# Powerbank_schematic.net
KiCad netlist of a schematic drawn in Altium Designer
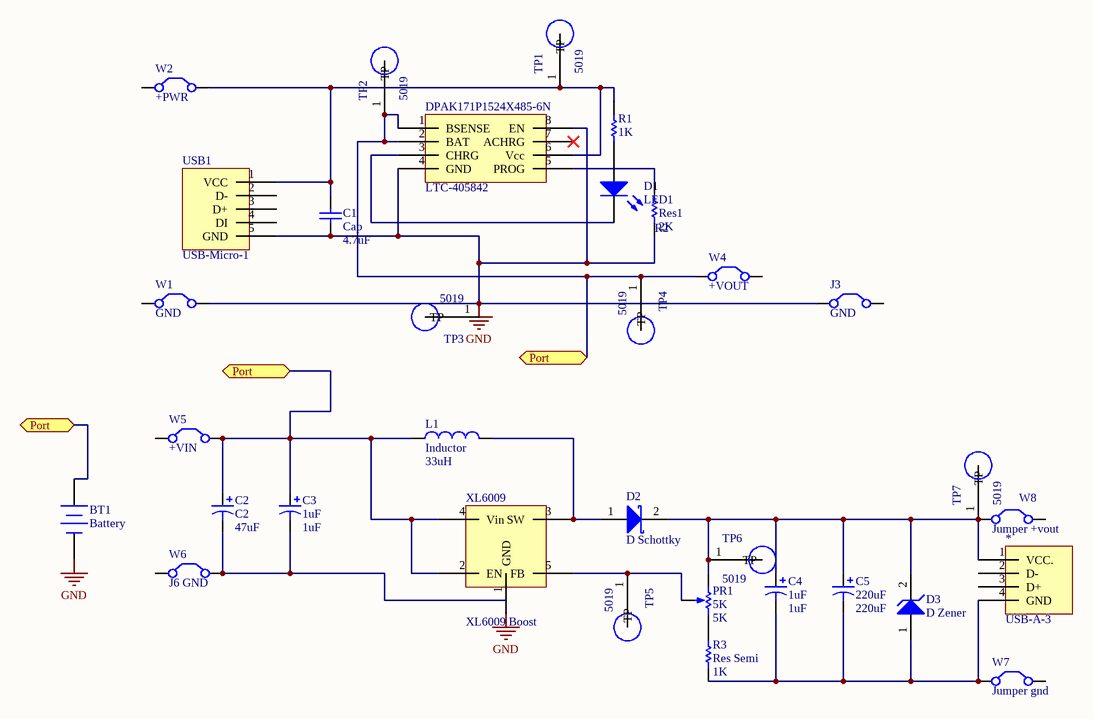
[diagram p0: Powerbank_schematic.SchDoc]

(export (version "E")
  (design (tool "Eeschema 10.0.6"))
  (components
    (comp (ref "*") (value "USB-A-3") (footprint "USB3") (libsource (lib "PCB_Project") (part "USB-A-3")))
    (comp (ref "BT1")
      (value "Battery")
      (footprint "BAT-2")
      (description "Multicell Battery")
      (fields (field (name "PUBLISHER") "Altium Limited"))
      (libsource (lib "Miscellaneous Devices") (part "Battery"))
    )
    (comp (ref "C1")
      (value "Cap")
      (footprint "RAD-0.3")
      (description "Capacitor")
      (fields (field (name "ALTIUM_VALUE") "4.7uF") (field (name "PUBLISHER") "Altium Limited"))
      (libsource (lib "Miscellaneous Devices") (part "Cap"))
    )
    (comp (ref "C2")
      (value "C2")
      (footprint "C0805")
      (description "Polarized Capacitor (Surface Mount)")
      (fields (field (name "ALTIUM_VALUE") "47uF") (field (name "PUBLISHER") "Altium Limited"))
      (libsource (lib "Miscellaneous Devices") (part "Cap Pol3"))
    )
    (comp (ref "C3")
      (value "1uF")
      (footprint "C0805")
      (description "Polarized Capacitor (Surface Mount)")
      (fields (field (name "ALTIUM_VALUE") "1uF") (field (name "PUBLISHER") "Altium Limited"))
      (libsource (lib "Miscellaneous Devices") (part "Cap Pol3"))
    )
    (comp (ref "C4")
      (value "1uF")
      (footprint "C0805")
      (description "Polarized Capacitor (Surface Mount)")
      (fields (field (name "ALTIUM_VALUE") "1uF") (field (name "PUBLISHER") "Altium Limited"))
      (libsource (lib "Miscellaneous Devices") (part "Cap Pol3"))
    )
    (comp (ref "C5")
      (value "220uF")
      (footprint "C0805")
      (description "Polarized Capacitor (Surface Mount)")
      (fields (field (name "ALTIUM_VALUE") "220uF") (field (name "PUBLISHER") "Altium Limited"))
      (libsource (lib "Miscellaneous Devices") (part "Cap Pol3"))
    )
    (comp (ref "D1")
      (value "LED1")
      (footprint "LED-1")
      (description "Typical RED GaAs LED")
      (fields (field (name "PUBLISHER") "Altium Limited"))
      (libsource (lib "Miscellaneous Devices") (part "LED1"))
    )
    (comp (ref "D2")
      (value "D Schottky")
      (footprint "SMB")
      (description "Schottky Diode")
      (fields (field (name "PUBLISHER") "Altium Limited"))
      (libsource (lib "Miscellaneous Devices") (part "D Schottky"))
    )
    (comp (ref "D3")
      (value "D Zener")
      (footprint "DIODE-0.7")
      (description "Zener Diode")
      (fields (field (name "PUBLISHER") "Altium Limited"))
      (libsource (lib "Miscellaneous Devices") (part "D Zener"))
    )
    (comp (ref "DPAK171P1524X485-6N")
      (value "LTC-405842")
      (footprint "DFN-8_DD")
      (libsource (lib "PCB_Project") (part "LTC-405842"))
    )
    (comp (ref "J3")
      (value "GND")
      (footprint "RAD-0.2")
      (description "Jumper Wire")
      (fields (field (name "PUBLISHER") "Altium Limited"))
      (libsource (lib "Miscellaneous Devices") (part "Jumper"))
    )
    (comp (ref "L1")
      (value "Inductor")
      (footprint "0402-A")
      (fields (field (name "ALTIUM_VALUE") "33uH") (field (name "PUBLISHER") "Altium Limited"))
      (libsource (lib "Miscellaneous Devices") (part "Inductor"))
    )
    (comp (ref "PR1")
      (value "5K")
      (footprint "VR5")
      (description "Potentiometer")
      (fields (field (name "ALTIUM_VALUE") "5K") (field (name "PUBLISHER") "Altium Limited"))
      (libsource (lib "Miscellaneous Devices") (part "RPot"))
    )
    (comp (ref "R1")
      (value "1K")
      (footprint "AXIAL-0.5")
      (description "Semiconductor Resistor")
      (fields (field (name "Comment") "Res Semi") (field (name "PUBLISHER") "Altium Limited"))
      (libsource (lib "Miscellaneous Devices") (part "Res Semi"))
    )
    (comp (ref "R2")
      (value "Res1")
      (footprint "AXIAL-0.3")
      (description "Resistor")
      (fields (field (name "ALTIUM_VALUE") "2K") (field (name "PUBLISHER") "Altium Limited"))
      (libsource (lib "Miscellaneous Devices") (part "Res1"))
    )
    (comp (ref "R3")
      (value "Res Semi")
      (footprint "AXIAL-0.5")
      (description "Semiconductor Resistor")
      (fields (field (name "ALTIUM_VALUE") "1K") (field (name "PUBLISHER") "Altium Limited"))
      (libsource (lib "Miscellaneous Devices") (part "Res Semi"))
    )
    (comp (ref "TP1")
      (value "5019")
      (footprint "TP380X203")
      (description "PC TEST POINT MINI SMD")
      (fields (field (name "MF") "Keystone"))
      (libsource (lib "5019") (part "5019"))
    )
    (comp (ref "TP2")
      (value "5019")
      (footprint "TP380X203")
      (description "PC TEST POINT MINI SMD")
      (fields (field (name "MF") "Keystone"))
      (libsource (lib "5019") (part "5019"))
    )
    (comp (ref "TP3")
      (value "5019")
      (footprint "TP380X203")
      (description "PC TEST POINT MINI SMD")
      (fields (field (name "MF") "Keystone"))
      (libsource (lib "5019") (part "5019"))
    )
    (comp (ref "TP4")
      (value "5019")
      (footprint "TP380X203")
      (description "PC TEST POINT MINI SMD")
      (fields (field (name "MF") "Keystone"))
      (libsource (lib "5019") (part "5019"))
    )
    (comp (ref "TP5")
      (value "5019")
      (footprint "TP380X203")
      (description "PC TEST POINT MINI SMD")
      (fields (field (name "MF") "Keystone"))
      (libsource (lib "5019") (part "5019"))
    )
    (comp (ref "TP6")
      (value "5019")
      (footprint "TP380X203")
      (description "PC TEST POINT MINI SMD")
      (fields (field (name "MF") "Keystone"))
      (libsource (lib "5019") (part "5019"))
    )
    (comp (ref "TP7")
      (value "5019")
      (footprint "TP380X203")
      (description "PC TEST POINT MINI SMD")
      (fields (field (name "MF") "Keystone"))
      (libsource (lib "5019") (part "5019"))
    )
    (comp (ref "USB1")
      (value "USB-Micro-1")
      (footprint "USB_Micro1")
      (libsource (lib "PCB_Project") (part "USB-Micro-1"))
    )
    (comp (ref "W1")
      (value "GND")
      (footprint "RAD-0.2")
      (description "Jumper Wire")
      (fields (field (name "PUBLISHER") "Altium Limited"))
      (libsource (lib "Miscellaneous Devices") (part "Jumper"))
    )
    (comp (ref "W2")
      (value "+PWR")
      (footprint "RAD-0.2")
      (description "Jumper Wire")
      (fields (field (name "PUBLISHER") "Altium Limited"))
      (libsource (lib "Miscellaneous Devices") (part "Jumper"))
    )
    (comp (ref "W4")
      (value "+VOUT")
      (footprint "RAD-0.2")
      (description "Jumper Wire")
      (fields (field (name "PUBLISHER") "Altium Limited"))
      (libsource (lib "Miscellaneous Devices") (part "Jumper"))
    )
    (comp (ref "W5")
      (value "+VIN")
      (footprint "RAD-0.2")
      (description "Jumper Wire")
      (fields (field (name "PUBLISHER") "Altium Limited"))
      (libsource (lib "Miscellaneous Devices") (part "Jumper"))
    )
    (comp (ref "W6")
      (value "J6 GND")
      (footprint "RAD-0.2")
      (description "Jumper Wire")
      (fields (field (name "PUBLISHER") "Altium Limited"))
      (libsource (lib "Miscellaneous Devices") (part "Jumper"))
    )
    (comp (ref "W7")
      (value "Jumper gnd")
      (footprint "RAD-0.2")
      (description "Jumper Wire")
      (fields (field (name "PUBLISHER") "Altium Limited"))
      (libsource (lib "Miscellaneous Devices") (part "Jumper"))
    )
    (comp (ref "W8")
      (value "Jumper +vout")
      (footprint "RAD-0.2")
      (description "Jumper Wire")
      (fields (field (name "PUBLISHER") "Altium Limited"))
      (libsource (lib "Miscellaneous Devices") (part "Jumper"))
    )
    (comp (ref "XL6009")
      (value "XL6009 Boost")
      (footprint "DPAK171P1524X485-6N")
      (libsource (lib "PCB_Project") (part "XL6009 Boost"))
    )
  )
  (nets
    (net (code "1") (name "/Port") (class "Default")
      (node (ref "BT1") (pin "1") (pinfunction "+_1") (pintype "passive"))
      (node (ref "C2") (pin "1") (pinfunction "1_1") (pintype "passive"))
      (node (ref "C3") (pin "1") (pinfunction "1_1") (pintype "passive"))
      (node (ref "DPAK171P1524X485-6N") (pin "1") (pinfunction "BSENSE_1") (pintype "passive"))
      (node (ref "DPAK171P1524X485-6N") (pin "2") (pinfunction "BAT_2") (pintype "passive"))
      (node (ref "L1") (pin "1") (pinfunction "1_1") (pintype "passive"))
      (node (ref "TP2") (pin "1") (pinfunction "TP_1") (pintype "passive"))
      (node (ref "TP4") (pin "1") (pinfunction "TP_1") (pintype "passive"))
      (node (ref "W4") (pin "1") (pinfunction "C1_1") (pintype "passive"))
      (node (ref "W5") (pin "2") (pinfunction "C2_2") (pintype "passive"))
      (node (ref "XL6009") (pin "2") (pinfunction "EN_2") (pintype "passive"))
      (node (ref "XL6009") (pin "4") (pinfunction "Vin_4") (pintype "passive"))
    )
    (net (code "2") (name "GND") (class "Default")
      (node (ref "BT1") (pin "2") (pinfunction "-_2") (pintype "passive"))
      (node (ref "C1") (pin "1") (pinfunction "1_1") (pintype "passive"))
      (node (ref "DPAK171P1524X485-6N") (pin "4") (pinfunction "GND_4") (pintype "passive"))
      (node (ref "DPAK171P1524X485-6N") (pin "8") (pinfunction "EN_8") (pintype "passive"))
      (node (ref "J3") (pin "1") (pinfunction "C1_1") (pintype "passive"))
      (node (ref "R2") (pin "1") (pinfunction "1_1") (pintype "passive"))
      (node (ref "USB1") (pin "5") (pinfunction "GND_5") (pintype "passive"))
      (node (ref "W1") (pin "2") (pinfunction "C2_2") (pintype "passive"))
      (node (ref "XL6009") (pin "1") (pinfunction "GND_1") (pintype "passive"))
    )
    (net (code "3") (name "Net-(*-GND)") (class "Default")
      (node (ref "*") (pin "4") (pinfunction "GND_4") (pintype "passive"))
      (node (ref "C4") (pin "2") (pinfunction "2_2") (pintype "passive"))
      (node (ref "C5") (pin "2") (pinfunction "2_2") (pintype "passive"))
      (node (ref "D3") (pin "1") (pinfunction "A_1") (pintype "passive"))
      (node (ref "R3") (pin "1") (pinfunction "1_1") (pintype "passive"))
      (node (ref "W7") (pin "1") (pinfunction "C1_1") (pintype "passive"))
    )
    (net (code "4") (name "Net-(*-VCC.)") (class "Default")
      (node (ref "*") (pin "1") (pinfunction "VCC._1") (pintype "passive"))
      (node (ref "C4") (pin "1") (pinfunction "1_1") (pintype "passive"))
      (node (ref "C5") (pin "1") (pinfunction "1_1") (pintype "passive"))
      (node (ref "D2") (pin "2") (pinfunction "K_2") (pintype "passive"))
      (node (ref "D3") (pin "2") (pinfunction "K_2") (pintype "passive"))
      (node (ref "PR1") (pin "1") (pinfunction "TOP_1") (pintype "passive"))
      (node (ref "TP6") (pin "1") (pinfunction "TP_1") (pintype "passive"))
      (node (ref "TP7") (pin "1") (pinfunction "TP_1") (pintype "passive"))
      (node (ref "W8") (pin "1") (pinfunction "C1_1") (pintype "passive"))
    )
    (net (code "5") (name "Net-(D1-A)") (class "Default")
      (node (ref "D1") (pin "1") (pinfunction "A_1") (pintype "passive"))
      (node (ref "R1") (pin "2") (pinfunction "2_2") (pintype "passive"))
    )
    (net (code "6") (name "Net-(D1-K)") (class "Default")
      (node (ref "D1") (pin "2") (pinfunction "K_2") (pintype "passive"))
      (node (ref "DPAK171P1524X485-6N") (pin "3") (pinfunction "CHRG_3") (pintype "passive"))
    )
    (net (code "7") (name "Net-(D2-A)") (class "Default")
      (node (ref "D2") (pin "1") (pinfunction "A_1") (pintype "passive"))
      (node (ref "L1") (pin "2") (pinfunction "2_2") (pintype "passive"))
      (node (ref "XL6009") (pin "3") (pinfunction "SW_3") (pintype "passive"))
    )
    (net (code "8") (name "Net-(DPAK171P1524X485-6N-PROG)") (class "Default")
      (node (ref "DPAK171P1524X485-6N") (pin "5") (pinfunction "PROG_5") (pintype "passive"))
      (node (ref "R2") (pin "2") (pinfunction "2_2") (pintype "passive"))
    )
    (net (code "9") (name "Net-(DPAK171P1524X485-6N-Vcc)") (class "Default")
      (node (ref "C1") (pin "2") (pinfunction "2_2") (pintype "passive"))
      (node (ref "DPAK171P1524X485-6N") (pin "6") (pinfunction "Vcc_6") (pintype "passive"))
      (node (ref "R1") (pin "1") (pinfunction "1_1") (pintype "passive"))
      (node (ref "TP1") (pin "1") (pinfunction "TP_1") (pintype "passive"))
      (node (ref "USB1") (pin "1") (pinfunction "VCC_1") (pintype "passive"))
      (node (ref "W2") (pin "2") (pinfunction "C2_2") (pintype "passive"))
    )
    (net (code "10") (name "Net-(PR1-BOT)") (class "Default")
      (node (ref "PR1") (pin "2") (pinfunction "BOT_2") (pintype "passive"))
      (node (ref "R3") (pin "2") (pinfunction "2_2") (pintype "passive"))
    )
    (net (code "11") (name "Net-(PR1-TAP)") (class "Default")
      (node (ref "PR1") (pin "3") (pinfunction "TAP_3") (pintype "passive"))
      (node (ref "TP5") (pin "1") (pinfunction "TP_1") (pintype "passive"))
      (node (ref "XL6009") (pin "5") (pinfunction "FB_5") (pintype "passive"))
    )
    (net (code "12") (name "Net-(W6-C2)") (class "Default")
      (node (ref "C2") (pin "2") (pinfunction "2_2") (pintype "passive"))
      (node (ref "C3") (pin "2") (pinfunction "2_2") (pintype "passive"))
      (node (ref "W6") (pin "2") (pinfunction "C2_2") (pintype "passive"))
    )
    (net (code "13") (name "unconnected-(*-D+-Pad3)") (class "Default")
      (node (ref "*") (pin "3") (pinfunction "D+_3") (pintype "passive"))
    )
    (net (code "14") (name "unconnected-(*-D--Pad2)") (class "Default")
      (node (ref "*") (pin "2") (pinfunction "D-_2") (pintype "passive"))
    )
    (net (code "15") (name "unconnected-(DPAK171P1524X485-6N-ACHRG-Pad7)") (class "Default")
      (node (ref "DPAK171P1524X485-6N") (pin "7") (pinfunction "ACHRG_7") (pintype "passive+no_connect"))
    )
    (net (code "16") (name "unconnected-(J3-C2-Pad2)") (class "Default")
      (node (ref "J3") (pin "2") (pinfunction "C2_2") (pintype "passive"))
    )
    (net (code "17") (name "unconnected-(TP3-TP-Pad1)") (class "Default")
      (node (ref "TP3") (pin "1") (pinfunction "TP_1") (pintype "passive"))
    )
    (net (code "18") (name "unconnected-(USB1-D+-Pad3)") (class "Default")
      (node (ref "USB1") (pin "3") (pinfunction "D+_3") (pintype "passive"))
    )
    (net (code "19") (name "unconnected-(USB1-D--Pad2)") (class "Default")
      (node (ref "USB1") (pin "2") (pinfunction "D-_2") (pintype "passive"))
    )
    (net (code "20") (name "unconnected-(USB1-DI-Pad4)") (class "Default")
      (node (ref "USB1") (pin "4") (pinfunction "DI_4") (pintype "passive"))
    )
    (net (code "21") (name "unconnected-(W1-C1-Pad1)") (class "Default")
      (node (ref "W1") (pin "1") (pinfunction "C1_1") (pintype "passive"))
    )
    (net (code "22") (name "unconnected-(W2-C1-Pad1)") (class "Default")
      (node (ref "W2") (pin "1") (pinfunction "C1_1") (pintype "passive"))
    )
    (net (code "23") (name "unconnected-(W4-C2-Pad2)") (class "Default")
      (node (ref "W4") (pin "2") (pinfunction "C2_2") (pintype "passive"))
    )
    (net (code "24") (name "unconnected-(W5-C1-Pad1)") (class "Default")
      (node (ref "W5") (pin "1") (pinfunction "C1_1") (pintype "passive"))
    )
    (net (code "25") (name "unconnected-(W6-C1-Pad1)") (class "Default")
      (node (ref "W6") (pin "1") (pinfunction "C1_1") (pintype "passive"))
    )
    (net (code "26") (name "unconnected-(W7-C2-Pad2)") (class "Default")
      (node (ref "W7") (pin "2") (pinfunction "C2_2") (pintype "passive"))
    )
    (net (code "27") (name "unconnected-(W8-C2-Pad2)") (class "Default")
      (node (ref "W8") (pin "2") (pinfunction "C2_2") (pintype "passive"))
    )
  )
)
